# people_counter_v2.net
KiCad netlist of a schematic drawn in EAGLE
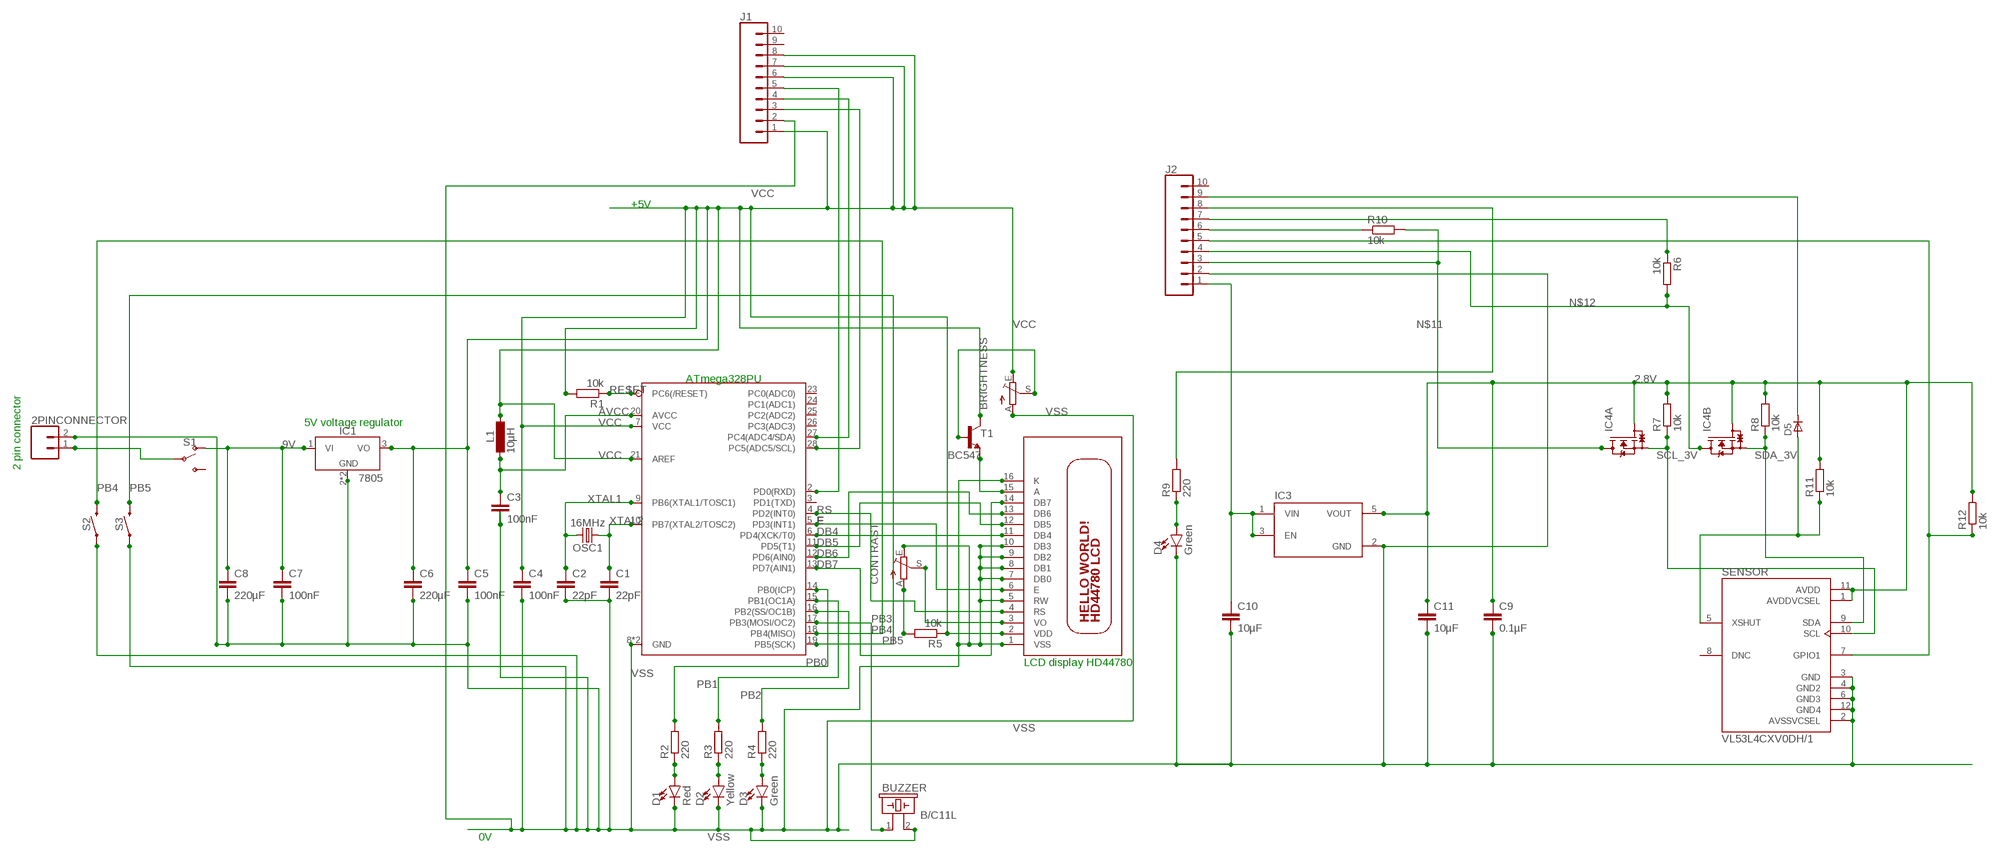
[diagram p0: schematic, sheet 1]

(export (version "E")
  (design (tool "Eeschema 10.0.6"))
  (components
    (comp (ref "2PINCONNECTOR")
      (value "CONN_02")
      (footprint "eagle-import:1X02")
      (libsource (lib "eagle-import") (part "CONN_02"))
    )
    (comp (ref "BRIGHTNESS")
      (value "TRIM_EU-PT10S")
      (footprint "eagle-import:PT-10S")
      (libsource (lib "eagle-import") (part "TRIM_EU-PT10S"))
    )
    (comp (ref "BUZZER")
      (value "B/C11L")
      (footprint "eagle-import:B_C11L")
      (libsource (lib "eagle-import") (part "B/C11L"))
    )
    (comp (ref "C1")
      (value "22pF")
      (footprint "eagle-import:C0805")
      (libsource (lib "eagle-import") (part "C-EUC0805"))
    )
    (comp (ref "C2")
      (value "22pF")
      (footprint "eagle-import:C0805")
      (libsource (lib "eagle-import") (part "C-EUC0805"))
    )
    (comp (ref "C3")
      (value "100nF")
      (footprint "eagle-import:C0805")
      (libsource (lib "eagle-import") (part "C-EUC0805"))
    )
    (comp (ref "C4")
      (value "100nF")
      (footprint "eagle-import:C0805")
      (libsource (lib "eagle-import") (part "C-EUC0805"))
    )
    (comp (ref "C5")
      (value "100nF")
      (footprint "eagle-import:C0805")
      (libsource (lib "eagle-import") (part "C-EUC0805"))
    )
    (comp (ref "C6")
      (value "220µF")
      (footprint "eagle-import:C0805")
      (libsource (lib "eagle-import") (part "C-EUC0805"))
    )
    (comp (ref "C7")
      (value "100nF")
      (footprint "eagle-import:C0805")
      (libsource (lib "eagle-import") (part "C-EUC0805"))
    )
    (comp (ref "C8")
      (value "220µF")
      (footprint "eagle-import:C0805")
      (libsource (lib "eagle-import") (part "C-EUC0805"))
    )
    (comp (ref "C9")
      (value "0.1µF")
      (footprint "eagle-import:C0805")
      (libsource (lib "eagle-import") (part "C-EUC0805"))
    )
    (comp (ref "C10")
      (value "10µF")
      (footprint "eagle-import:C0805")
      (libsource (lib "eagle-import") (part "C-EUC0805"))
    )
    (comp (ref "C11")
      (value "10µF")
      (footprint "eagle-import:C0805")
      (libsource (lib "eagle-import") (part "C-EUC0805"))
    )
    (comp (ref "CONTRAST")
      (value "TRIM_EU-PT10S")
      (footprint "eagle-import:PT-10S")
      (libsource (lib "eagle-import") (part "TRIM_EU-PT10S"))
    )
    (comp (ref "D1")
      (value "Red")
      (footprint "eagle-import:LED-0603")
      (libsource (lib "eagle-import") (part "LED-RED-0603-WE"))
    )
    (comp (ref "D2")
      (value "Yellow")
      (footprint "eagle-import:LED-0603")
      (libsource (lib "eagle-import") (part "LED-YELLOW-0603-WE"))
    )
    (comp (ref "D3")
      (value "Green")
      (footprint "eagle-import:LED-0603")
      (libsource (lib "eagle-import") (part "LED-GREEN-0603-WE"))
    )
    (comp (ref "D4")
      (value "Green")
      (footprint "eagle-import:LED-0603")
      (libsource (lib "eagle-import") (part "LED-GREEN-0603-WE"))
    )
    (comp (ref "D5")
      (value "1N4148WS")
      (footprint "eagle-import:SOD323F")
      (libsource (lib "eagle-import") (part "1N4148WS"))
    )
    (comp (ref "IC1")
      (value "7805")
      (footprint "eagle-import:SOT230P700X170-4")
      (fields (field (name "MANUFACTURER") "Generic"))
      (libsource (lib "eagle-import") (part "LM7805_SOT223"))
    )
    (comp (ref "IC2")
      (value "328P")
      (footprint "eagle-import:DIP28")
      (libsource (lib "eagle-import") (part "ATMEGA328P_PDIP"))
    )
    (comp (ref "IC3")
      (value "MIC5504-2.8YM5-TR")
      (footprint "eagle-import:SOT95P280X145-5N")
      (fields (field (name "MF") "Microchip"))
      (libsource (lib "eagle-import") (part "MIC5504-2.8YM5-TR"))
    )
    (comp (ref "IC4")
      (value "DMN63D8LDW-7")
      (footprint "eagle-import:SOT363")
      (fields (field (name "MF") "Diodes Inc."))
      (libsource (lib "eagle-import") (part "DMN63D8LDW-7"))
    )
    (comp (ref "J1")
      (value "CONN_10\"")
      (footprint "eagle-import:1X10")
      (libsource (lib "eagle-import") (part "CONN_10{dblquote}"))
    )
    (comp (ref "J2")
      (value "CONN_10\"")
      (footprint "eagle-import:1X10")
      (libsource (lib "eagle-import") (part "CONN_10{dblquote}"))
    )
    (comp (ref "L1")
      (value "10µH")
      (footprint "eagle-import:L1812")
      (libsource (lib "eagle-import") (part "L-EUL1812"))
    )
    (comp (ref "OSC1")
      (value "16MHz")
      (footprint "eagle-import:HC49US")
      (libsource (lib "eagle-import") (part "CRYSTAL-16MHZPTH-HC49US"))
    )
    (comp (ref "R1")
      (value "10k")
      (footprint "eagle-import:R0603")
      (libsource (lib "eagle-import") (part "R-EU_R0603"))
    )
    (comp (ref "R2")
      (value "220")
      (footprint "eagle-import:R0603")
      (libsource (lib "eagle-import") (part "R-EU_R0603"))
    )
    (comp (ref "R3")
      (value "220")
      (footprint "eagle-import:R0603")
      (libsource (lib "eagle-import") (part "R-EU_R0603"))
    )
    (comp (ref "R4")
      (value "220")
      (footprint "eagle-import:R0603")
      (libsource (lib "eagle-import") (part "R-EU_R0603"))
    )
    (comp (ref "R5")
      (value "10k")
      (footprint "eagle-import:R0603")
      (libsource (lib "eagle-import") (part "R-EU_R0603"))
    )
    (comp (ref "R6")
      (value "10k")
      (footprint "eagle-import:R0603")
      (libsource (lib "eagle-import") (part "R-EU_R0603"))
    )
    (comp (ref "R7")
      (value "10k")
      (footprint "eagle-import:R0603")
      (libsource (lib "eagle-import") (part "R-EU_R0603"))
    )
    (comp (ref "R8")
      (value "10k")
      (footprint "eagle-import:R0603")
      (libsource (lib "eagle-import") (part "R-EU_R0603"))
    )
    (comp (ref "R9")
      (value "220")
      (footprint "eagle-import:R0603")
      (libsource (lib "eagle-import") (part "R-EU_R0603"))
    )
    (comp (ref "R10")
      (value "10k")
      (footprint "eagle-import:R0603")
      (libsource (lib "eagle-import") (part "R-EU_R0603"))
    )
    (comp (ref "R11")
      (value "10k")
      (footprint "eagle-import:R0603")
      (libsource (lib "eagle-import") (part "R-EU_R0603"))
    )
    (comp (ref "R12")
      (value "10k")
      (footprint "eagle-import:R0603")
      (libsource (lib "eagle-import") (part "R-EU_R0603"))
    )
    (comp (ref "S1")
      (value "SWITCH-SPDT-PTH-11.6X4.0MM")
      (footprint "eagle-import:SWITCH_SPDT_PTH_11.6X4.0MM")
      (libsource (lib "eagle-import") (part "SWITCH-SPDT-PTH-11.6X4.0MM"))
    )
    (comp (ref "S2")
      (value "MOMENTARY-SWITCH-SPST-PTH-6.0MM")
      (footprint "eagle-import:TACTILE_SWITCH_PTH_6.0MM")
      (libsource (lib "eagle-import") (part "MOMENTARY-SWITCH-SPST-PTH-6.0MM"))
    )
    (comp (ref "S3")
      (value "MOMENTARY-SWITCH-SPST-PTH-6.0MM")
      (footprint "eagle-import:TACTILE_SWITCH_PTH_6.0MM")
      (libsource (lib "eagle-import") (part "MOMENTARY-SWITCH-SPST-PTH-6.0MM"))
    )
    (comp (ref "SENSOR")
      (value "VL53L4CXV0DH/1")
      (footprint "eagle-import:XCDR_VL53L4CXV0DH_1")
      (fields (field (name "MF") "STMicroelectronics"))
      (libsource (lib "eagle-import") (part "VL53L4CXV0DH/1"))
    )
    (comp (ref "T1")
      (value "BC547")
      (footprint "eagle-import:TO92")
      (libsource (lib "eagle-import") (part "BC547"))
    )
    (comp (ref "X1")
      (value "HD44780LCD-1602")
      (footprint "eagle-import:LCD1602")
      (libsource (lib "eagle-import") (part "HD44780LCD-1602"))
    )
  )
  (nets
    (net (code "1") (name "2.8V") (class "Default")
      (node (ref "C11") (pin "1") (pinfunction "1_1") (pintype "passive"))
      (node (ref "C9") (pin "1") (pinfunction "1_1") (pintype "passive"))
      (node (ref "IC3") (pin "5") (pinfunction "VOUT_5") (pintype "output"))
      (node (ref "IC4") (pin "G1") (pinfunction "G_G1") (pintype "passive"))
      (node (ref "IC4") (pin "G2") (pinfunction "G_G2") (pintype "passive"))
      (node (ref "R11") (pin "2") (pinfunction "2_2") (pintype "passive"))
      (node (ref "R12") (pin "2") (pinfunction "2_2") (pintype "passive"))
      (node (ref "R7") (pin "2") (pinfunction "2_2") (pintype "passive"))
      (node (ref "R8") (pin "2") (pinfunction "2_2") (pintype "passive"))
      (node (ref "SENSOR") (pin "1") (pinfunction "AVDDVCSEL_1") (pintype "power_in"))
      (node (ref "SENSOR") (pin "11") (pinfunction "AVDD_11") (pintype "power_in"))
    )
    (net (code "2") (name "9V") (class "Default")
      (node (ref "C7") (pin "1") (pinfunction "1_1") (pintype "passive"))
      (node (ref "C8") (pin "1") (pinfunction "1_1") (pintype "passive"))
      (node (ref "IC1") (pin "1") (pinfunction "VI_1") (pintype "input"))
      (node (ref "S1") (pin "1") (pinfunction "O_1") (pintype "passive"))
    )
    (net (code "3") (name "AVCC") (class "Default")
      (node (ref "C3") (pin "1") (pinfunction "1_1") (pintype "passive"))
      (node (ref "IC2") (pin "20") (pinfunction "AVCC_20") (pintype "bidirectional"))
      (node (ref "L1") (pin "2") (pinfunction "2_2") (pintype "passive"))
    )
    (net (code "4") (name "DB4") (class "Default")
      (node (ref "IC2") (pin "6") (pinfunction "PD4(XCK/T0)_6") (pintype "bidirectional"))
      (node (ref "X1") (pin "11") (pinfunction "DB4_11") (pintype "bidirectional"))
    )
    (net (code "5") (name "DB5") (class "Default")
      (node (ref "IC2") (pin "11") (pinfunction "PD5(T1)_11") (pintype "bidirectional"))
      (node (ref "X1") (pin "12") (pinfunction "DB5_12") (pintype "bidirectional"))
    )
    (net (code "6") (name "DB6") (class "Default")
      (node (ref "IC2") (pin "12") (pinfunction "PD6(AIN0)_12") (pintype "bidirectional"))
      (node (ref "X1") (pin "13") (pinfunction "DB6_13") (pintype "bidirectional"))
    )
    (net (code "7") (name "DB7") (class "Default")
      (node (ref "IC2") (pin "13") (pinfunction "PD7(AIN1)_13") (pintype "bidirectional"))
      (node (ref "X1") (pin "14") (pinfunction "DB7_14") (pintype "bidirectional"))
    )
    (net (code "8") (name "E") (class "Default")
      (node (ref "IC2") (pin "5") (pinfunction "PD3(INT1)_5") (pintype "bidirectional"))
      (node (ref "X1") (pin "6") (pinfunction "E_6") (pintype "input"))
    )
    (net (code "9") (name "N$11") (class "Default")
      (node (ref "IC4") (pin "D1") (pinfunction "D_D1") (pintype "passive"))
      (node (ref "J2") (pin "3") (pinfunction "3_3") (pintype "passive"))
      (node (ref "R10") (pin "2") (pinfunction "2_2") (pintype "passive"))
    )
    (net (code "10") (name "N$12") (class "Default")
      (node (ref "IC4") (pin "D2") (pinfunction "D_D2") (pintype "passive"))
      (node (ref "J2") (pin "4") (pinfunction "4_4") (pintype "passive"))
      (node (ref "R6") (pin "2") (pinfunction "2_2") (pintype "passive"))
    )
    (net (code "11") (name "Net-(CONTRAST-PadA)") (class "Default")
      (node (ref "CONTRAST") (pin "A") (pinfunction "A_A") (pintype "passive"))
      (node (ref "R5") (pin "2") (pinfunction "2_2") (pintype "passive"))
    )
    (net (code "12") (name "Net-(D1-PadA)") (class "Default")
      (node (ref "D1") (pin "A") (pinfunction "A_A") (pintype "passive"))
      (node (ref "R2") (pin "1") (pinfunction "1_1") (pintype "passive"))
    )
    (net (code "13") (name "Net-(D2-PadA)") (class "Default")
      (node (ref "D2") (pin "A") (pinfunction "A_A") (pintype "passive"))
      (node (ref "R3") (pin "1") (pinfunction "1_1") (pintype "passive"))
    )
    (net (code "14") (name "Net-(D3-PadA)") (class "Default")
      (node (ref "D3") (pin "A") (pinfunction "A_A") (pintype "passive"))
      (node (ref "R4") (pin "1") (pinfunction "1_1") (pintype "passive"))
    )
    (net (code "15") (name "Net-(D4-PadA)") (class "Default")
      (node (ref "D4") (pin "A") (pinfunction "A_A") (pintype "passive"))
      (node (ref "R9") (pin "1") (pinfunction "1_1") (pintype "passive"))
    )
    (net (code "16") (name "Net-(D5-PadC)") (class "Default")
      (node (ref "D5") (pin "C") (pinfunction "C_C") (pintype "passive"))
      (node (ref "J2") (pin "9") (pinfunction "9_9") (pintype "passive"))
    )
    (net (code "17") (name "Net-(IC2-PC4(ADC4{slash}SDA))") (class "Default")
      (node (ref "IC2") (pin "27") (pinfunction "PC4(ADC4/SDA)_27") (pintype "bidirectional"))
      (node (ref "J1") (pin "4") (pinfunction "4_4") (pintype "passive"))
    )
    (net (code "18") (name "Net-(IC2-PC5(ADC5{slash}SCL))") (class "Default")
      (node (ref "IC2") (pin "28") (pinfunction "PC5(ADC5/SCL)_28") (pintype "bidirectional"))
      (node (ref "J1") (pin "3") (pinfunction "3_3") (pintype "passive"))
    )
    (net (code "19") (name "Net-(IC2-PD0(RXD))") (class "Default")
      (node (ref "IC2") (pin "2") (pinfunction "PD0(RXD)_2") (pintype "bidirectional"))
      (node (ref "J1") (pin "5") (pinfunction "5_5") (pintype "passive"))
    )
    (net (code "20") (name "Net-(IC3-EN)") (class "Default")
      (node (ref "C10") (pin "1") (pinfunction "1_1") (pintype "passive"))
      (node (ref "IC3") (pin "1") (pinfunction "VIN_1") (pintype "input"))
      (node (ref "IC3") (pin "3") (pinfunction "EN_3") (pintype "input"))
      (node (ref "J2") (pin "1") (pinfunction "1_1") (pintype "passive"))
    )
    (net (code "21") (name "Net-(J2-Pad6)") (class "Default")
      (node (ref "J2") (pin "6") (pinfunction "6_6") (pintype "passive"))
      (node (ref "R10") (pin "1") (pinfunction "1_1") (pintype "passive"))
    )
    (net (code "22") (name "Net-(J2-Pad7)") (class "Default")
      (node (ref "J2") (pin "7") (pinfunction "7_7") (pintype "passive"))
      (node (ref "R6") (pin "1") (pinfunction "1_1") (pintype "passive"))
    )
    (net (code "23") (name "Net-(J2-Pad8)") (class "Default")
      (node (ref "J2") (pin "8") (pinfunction "8_8") (pintype "passive"))
      (node (ref "R9") (pin "2") (pinfunction "2_2") (pintype "passive"))
    )
    (net (code "24") (name "Net-(S1-P)") (class "Default")
      (node (ref "2PINCONNECTOR") (pin "1") (pinfunction "1_1") (pintype "passive"))
      (node (ref "S1") (pin "2") (pinfunction "P_2") (pintype "passive"))
    )
    (net (code "25") (name "Net-(SENSOR-GPIO1)") (class "Default")
      (node (ref "J2") (pin "5") (pinfunction "5_5") (pintype "passive"))
      (node (ref "R12") (pin "1") (pinfunction "1_1") (pintype "passive"))
      (node (ref "SENSOR") (pin "7") (pinfunction "GPIO1_7") (pintype "output"))
    )
    (net (code "26") (name "Net-(SENSOR-XSHUT)") (class "Default")
      (node (ref "D5") (pin "A") (pinfunction "A_A") (pintype "passive"))
      (node (ref "R11") (pin "1") (pinfunction "1_1") (pintype "passive"))
      (node (ref "SENSOR") (pin "5") (pinfunction "XSHUT_5") (pintype "input"))
    )
    (net (code "27") (name "Net-(T1-B)") (class "Default")
      (node (ref "BRIGHTNESS") (pin "S") (pinfunction "S_S") (pintype "passive"))
      (node (ref "T1") (pin "2") (pinfunction "B_2") (pintype "passive"))
    )
    (net (code "28") (name "Net-(T1-E)") (class "Default")
      (node (ref "T1") (pin "1") (pinfunction "E_1") (pintype "passive"))
      (node (ref "X1") (pin "15") (pinfunction "A_15") (pintype "input"))
    )
    (net (code "29") (name "Net-(X1-VO)") (class "Default")
      (node (ref "CONTRAST") (pin "S") (pinfunction "S_S") (pintype "passive"))
      (node (ref "X1") (pin "3") (pinfunction "VO_3") (pintype "input"))
    )
    (net (code "30") (name "PB0") (class "Default")
      (node (ref "IC2") (pin "14") (pinfunction "PB0(ICP)_14") (pintype "bidirectional"))
      (node (ref "R2") (pin "2") (pinfunction "2_2") (pintype "passive"))
    )
    (net (code "31") (name "PB1") (class "Default")
      (node (ref "IC2") (pin "15") (pinfunction "PB1(OC1A)_15") (pintype "bidirectional"))
      (node (ref "R3") (pin "2") (pinfunction "2_2") (pintype "passive"))
    )
    (net (code "32") (name "PB2") (class "Default")
      (node (ref "IC2") (pin "16") (pinfunction "PB2(SS/OC1B)_16") (pintype "bidirectional"))
      (node (ref "R4") (pin "2") (pinfunction "2_2") (pintype "passive"))
    )
    (net (code "33") (name "PB3") (class "Default")
      (node (ref "BUZZER") (pin "1") (pinfunction "1_1") (pintype "passive"))
      (node (ref "IC2") (pin "17") (pinfunction "PB3(MOSI/OC2)_17") (pintype "bidirectional"))
    )
    (net (code "34") (name "PB4") (class "Default")
      (node (ref "IC2") (pin "18") (pinfunction "PB4(MISO)_18") (pintype "bidirectional"))
      (node (ref "S2") (pin "3") (pinfunction "2_3") (pintype "passive"))
    )
    (net (code "35") (name "PB5") (class "Default")
      (node (ref "IC2") (pin "19") (pinfunction "PB5(SCK)_19") (pintype "bidirectional"))
      (node (ref "S3") (pin "3") (pinfunction "2_3") (pintype "passive"))
    )
    (net (code "36") (name "RESET") (class "Default")
      (node (ref "IC2") (pin "1") (pinfunction "PC6(/RESET)_1") (pintype "bidirectional"))
      (node (ref "R1") (pin "1") (pinfunction "1_1") (pintype "passive"))
    )
    (net (code "37") (name "RS") (class "Default")
      (node (ref "IC2") (pin "4") (pinfunction "PD2(INT0)_4") (pintype "bidirectional"))
      (node (ref "X1") (pin "4") (pinfunction "RS_4") (pintype "input"))
    )
    (net (code "38") (name "SCL_3V") (class "Default")
      (node (ref "IC4") (pin "S1") (pinfunction "S_S1") (pintype "passive"))
      (node (ref "R7") (pin "1") (pinfunction "1_1") (pintype "passive"))
      (node (ref "SENSOR") (pin "10") (pinfunction "SCL_10") (pintype "input"))
    )
    (net (code "39") (name "SDA_3V") (class "Default")
      (node (ref "IC4") (pin "S2") (pinfunction "S_S2") (pintype "passive"))
      (node (ref "R8") (pin "1") (pinfunction "1_1") (pintype "passive"))
      (node (ref "SENSOR") (pin "9") (pinfunction "SDA_9") (pintype "bidirectional"))
    )
    (net (code "40") (name "VCC") (class "Default")
      (node (ref "BRIGHTNESS") (pin "E") (pinfunction "E_E") (pintype "passive"))
      (node (ref "C4") (pin "1") (pinfunction "1_1") (pintype "passive"))
      (node (ref "C5") (pin "1") (pinfunction "1_1") (pintype "passive"))
      (node (ref "C6") (pin "1") (pinfunction "1_1") (pintype "passive"))
      (node (ref "IC1") (pin "3") (pinfunction "VO_3") (pintype "output"))
      (node (ref "IC2") (pin "21") (pinfunction "AREF_21") (pintype "bidirectional"))
      (node (ref "IC2") (pin "7") (pinfunction "VCC_7") (pintype "bidirectional"))
      (node (ref "J1") (pin "1") (pinfunction "1_1") (pintype "passive"))
      (node (ref "J1") (pin "6") (pinfunction "6_6") (pintype "passive"))
      (node (ref "J1") (pin "7") (pinfunction "7_7") (pintype "passive"))
      (node (ref "J1") (pin "8") (pinfunction "8_8") (pintype "passive"))
      (node (ref "L1") (pin "1") (pinfunction "1_1") (pintype "passive"))
      (node (ref "R1") (pin "2") (pinfunction "2_2") (pintype "passive"))
      (node (ref "R5") (pin "1") (pinfunction "1_1") (pintype "passive"))
      (node (ref "T1") (pin "3") (pinfunction "C_3") (pintype "passive"))
      (node (ref "X1") (pin "2") (pinfunction "VDD_2") (pintype "power_in"))
    )
    (net (code "41") (name "VSS") (class "Default")
      (node (ref "2PINCONNECTOR") (pin "2") (pinfunction "2_2") (pintype "passive"))
      (node (ref "BRIGHTNESS") (pin "A") (pinfunction "A_A") (pintype "passive"))
      (node (ref "BUZZER") (pin "2") (pinfunction "2_2") (pintype "passive"))
      (node (ref "C1") (pin "2") (pinfunction "2_2") (pintype "passive"))
      (node (ref "C10") (pin "2") (pinfunction "2_2") (pintype "passive"))
      (node (ref "C11") (pin "2") (pinfunction "2_2") (pintype "passive"))
      (node (ref "C2") (pin "2") (pinfunction "2_2") (pintype "passive"))
      (node (ref "C3") (pin "2") (pinfunction "2_2") (pintype "passive"))
      (node (ref "C4") (pin "2") (pinfunction "2_2") (pintype "passive"))
      (node (ref "C5") (pin "2") (pinfunction "2_2") (pintype "passive"))
      (node (ref "C6") (pin "2") (pinfunction "2_2") (pintype "passive"))
      (node (ref "C7") (pin "2") (pinfunction "2_2") (pintype "passive"))
      (node (ref "C8") (pin "2") (pinfunction "2_2") (pintype "passive"))
      (node (ref "C9") (pin "2") (pinfunction "2_2") (pintype "passive"))
      (node (ref "CONTRAST") (pin "E") (pinfunction "E_E") (pintype "passive"))
      (node (ref "D1") (pin "C") (pinfunction "C_C") (pintype "passive"))
      (node (ref "D2") (pin "C") (pinfunction "C_C") (pintype "passive"))
      (node (ref "D3") (pin "C") (pinfunction "C_C") (pintype "passive"))
      (node (ref "D4") (pin "C") (pinfunction "C_C") (pintype "passive"))
      (node (ref "IC1") (pin "2") (pinfunction "GND_2") (pintype "passive"))
      (node (ref "IC1") (pin "4") (pinfunction "GND_4") (pintype "passive"))
      (node (ref "IC2") (pin "22") (pinfunction "GND_22") (pintype "bidirectional"))
      (node (ref "IC2") (pin "8") (pinfunction "GND_8") (pintype "bidirectional"))
      (node (ref "IC3") (pin "2") (pinfunction "GND_2") (pintype "power_in"))
      (node (ref "J1") (pin "2") (pinfunction "2_2") (pintype "passive"))
      (node (ref "J2") (pin "2") (pinfunction "2_2") (pintype "passive"))
      (node (ref "S2") (pin "1") (pinfunction "1_1") (pintype "passive"))
      (node (ref "S3") (pin "1") (pinfunction "1_1") (pintype "passive"))
      (node (ref "SENSOR") (pin "12") (pinfunction "GND4_12") (pintype "power_in"))
      (node (ref "SENSOR") (pin "2") (pinfunction "AVSSVCSEL_2") (pintype "power_in"))
      (node (ref "SENSOR") (pin "3") (pinfunction "GND_3") (pintype "power_in"))
      (node (ref "SENSOR") (pin "4") (pinfunction "GND2_4") (pintype "power_in"))
      (node (ref "SENSOR") (pin "6") (pinfunction "GND3_6") (pintype "power_in"))
      (node (ref "X1") (pin "1") (pinfunction "VSS_1") (pintype "power_in"))
      (node (ref "X1") (pin "10") (pinfunction "DB3_10") (pintype "bidirectional"))
      (node (ref "X1") (pin "16") (pinfunction "K_16") (pintype "input"))
      (node (ref "X1") (pin "5") (pinfunction "RW_5") (pintype "input"))
      (node (ref "X1") (pin "7") (pinfunction "DB0_7") (pintype "bidirectional"))
      (node (ref "X1") (pin "8") (pinfunction "DB1_8") (pintype "bidirectional"))
      (node (ref "X1") (pin "9") (pinfunction "DB2_9") (pintype "bidirectional"))
    )
    (net (code "42") (name "XTAL1") (class "Default")
      (node (ref "C2") (pin "1") (pinfunction "1_1") (pintype "passive"))
      (node (ref "IC2") (pin "9") (pinfunction "PB6(XTAL1/TOSC1)_9") (pintype "bidirectional"))
      (node (ref "OSC1") (pin "2") (pinfunction "2_2") (pintype "passive"))
    )
    (net (code "43") (name "XTAL2") (class "Default")
      (node (ref "C1") (pin "1") (pinfunction "1_1") (pintype "passive"))
      (node (ref "IC2") (pin "10") (pinfunction "PB7(XTAL2/TOSC2)_10") (pintype "bidirectional"))
      (node (ref "OSC1") (pin "1") (pinfunction "1_1") (pintype "passive"))
    )
    (net (code "44") (name "unconnected-(IC2-PC0(ADC0)-Pad23)") (class "Default")
      (node (ref "IC2") (pin "23") (pinfunction "PC0(ADC0)_23") (pintype "bidirectional"))
    )
    (net (code "45") (name "unconnected-(IC2-PC1(ADC1)-Pad24)") (class "Default")
      (node (ref "IC2") (pin "24") (pinfunction "PC1(ADC1)_24") (pintype "bidirectional"))
    )
    (net (code "46") (name "unconnected-(IC2-PC2(ADC2)-Pad25)") (class "Default")
      (node (ref "IC2") (pin "25") (pinfunction "PC2(ADC2)_25") (pintype "bidirectional"))
    )
    (net (code "47") (name "unconnected-(IC2-PC3(ADC3)-Pad26)") (class "Default")
      (node (ref "IC2") (pin "26") (pinfunction "PC3(ADC3)_26") (pintype "bidirectional"))
    )
    (net (code "48") (name "unconnected-(IC2-PD1(TXD)-Pad3)") (class "Default")
      (node (ref "IC2") (pin "3") (pinfunction "PD1(TXD)_3") (pintype "bidirectional"))
    )
    (net (code "49") (name "unconnected-(J1-Pad9)") (class "Default")
      (node (ref "J1") (pin "9") (pinfunction "9_9") (pintype "passive"))
    )
    (net (code "50") (name "unconnected-(J1-Pad10)") (class "Default")
      (node (ref "J1") (pin "10") (pinfunction "10_10") (pintype "passive"))
    )
    (net (code "51") (name "unconnected-(J2-Pad10)") (class "Default")
      (node (ref "J2") (pin "10") (pinfunction "10_10") (pintype "passive"))
    )
    (net (code "52") (name "unconnected-(S1-S-Pad3)") (class "Default")
      (node (ref "S1") (pin "3") (pinfunction "S_3") (pintype "passive"))
    )
    (net (code "53") (name "unconnected-(SENSOR-DNC-Pad8)") (class "Default")
      (node (ref "SENSOR") (pin "8") (pinfunction "DNC_8") (pintype "no_connect"))
    )
  )
)
